# 7Seg.net
KiCad netlist of a schematic drawn in Altium Designer
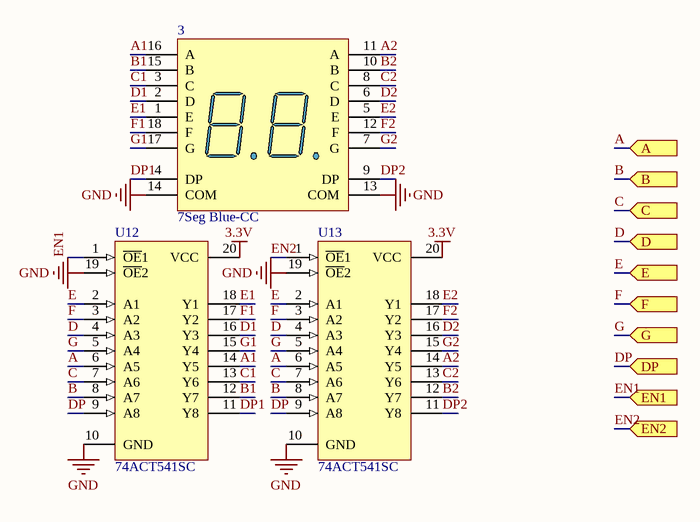
[diagram p0: 7Seg.SchDoc]

(export (version "E")
  (design (tool "Eeschema 10.0.6"))
  (components
    (comp (ref "3")
      (value "7Seg Blue-CC")
      (footprint "7Segment Dual")
      (description "General Purpose Blue 7-Segment Display: CC, RH DP, Gray Surface")
      (fields (field (name "PUBLISHER") "Altium Limited"))
      (libsource (lib "KN2CLib") (part "7Seg Blue-CC_Dual"))
    )
    (comp (ref "U12")
      (value "74ACT541SC")
      (footprint "M20B_N")
      (description "Octal Buffer/Line Driver with 3-State Output")
      (fields (field (name "PUBLISHER") "Altium Limited"))
      (libsource (lib "FSC Logic Buffer Line Driver") (part "74ACT541SC"))
    )
    (comp (ref "U13")
      (value "74ACT541SC")
      (footprint "M20B_N")
      (description "Octal Buffer/Line Driver with 3-State Output")
      (fields (field (name "PUBLISHER") "Altium Limited"))
      (libsource (lib "FSC Logic Buffer Line Driver") (part "74ACT541SC"))
    )
  )
  (nets
    (net (code "1") (name "/A") (class "Default")
      (node (ref "U12") (pin "6") (pinfunction "A5_6") (pintype "input"))
      (node (ref "U13") (pin "6") (pinfunction "A5_6") (pintype "input"))
    )
    (net (code "2") (name "/A1") (class "Default")
      (node (ref "3") (pin "16") (pinfunction "A_16") (pintype "passive"))
      (node (ref "U12") (pin "14") (pinfunction "Y5_14") (pintype "tri_state"))
    )
    (net (code "3") (name "/A2") (class "Default")
      (node (ref "3") (pin "11") (pinfunction "A_11") (pintype "passive"))
      (node (ref "U13") (pin "14") (pinfunction "Y5_14") (pintype "tri_state"))
    )
    (net (code "4") (name "/B") (class "Default")
      (node (ref "U12") (pin "8") (pinfunction "A7_8") (pintype "input"))
      (node (ref "U13") (pin "8") (pinfunction "A7_8") (pintype "input"))
    )
    (net (code "5") (name "/B1") (class "Default")
      (node (ref "3") (pin "15") (pinfunction "B_15") (pintype "passive"))
      (node (ref "U12") (pin "12") (pinfunction "Y7_12") (pintype "tri_state"))
    )
    (net (code "6") (name "/B2") (class "Default")
      (node (ref "3") (pin "10") (pinfunction "B_10") (pintype "passive"))
      (node (ref "U13") (pin "12") (pinfunction "Y7_12") (pintype "tri_state"))
    )
    (net (code "7") (name "/C") (class "Default")
      (node (ref "U12") (pin "7") (pinfunction "A6_7") (pintype "input"))
      (node (ref "U13") (pin "7") (pinfunction "A6_7") (pintype "input"))
    )
    (net (code "8") (name "/C1") (class "Default")
      (node (ref "3") (pin "3") (pinfunction "C_3") (pintype "passive"))
      (node (ref "U12") (pin "13") (pinfunction "Y6_13") (pintype "tri_state"))
    )
    (net (code "9") (name "/C2") (class "Default")
      (node (ref "3") (pin "8") (pinfunction "C_8") (pintype "passive"))
      (node (ref "U13") (pin "13") (pinfunction "Y6_13") (pintype "tri_state"))
    )
    (net (code "10") (name "/D") (class "Default")
      (node (ref "U12") (pin "4") (pinfunction "A3_4") (pintype "input"))
      (node (ref "U13") (pin "4") (pinfunction "A3_4") (pintype "input"))
    )
    (net (code "11") (name "/D1") (class "Default")
      (node (ref "3") (pin "2") (pinfunction "D_2") (pintype "passive"))
      (node (ref "U12") (pin "16") (pinfunction "Y3_16") (pintype "tri_state"))
    )
    (net (code "12") (name "/D2") (class "Default")
      (node (ref "3") (pin "6") (pinfunction "D_6") (pintype "passive"))
      (node (ref "U13") (pin "16") (pinfunction "Y3_16") (pintype "tri_state"))
    )
    (net (code "13") (name "/DP") (class "Default")
      (node (ref "U12") (pin "9") (pinfunction "A8_9") (pintype "input"))
      (node (ref "U13") (pin "9") (pinfunction "A8_9") (pintype "input"))
    )
    (net (code "14") (name "/DP1") (class "Default")
      (node (ref "3") (pin "4") (pinfunction "DP_4") (pintype "passive"))
      (node (ref "U12") (pin "11") (pinfunction "Y8_11") (pintype "tri_state"))
    )
    (net (code "15") (name "/DP2") (class "Default")
      (node (ref "3") (pin "9") (pinfunction "DP_9") (pintype "passive"))
      (node (ref "U13") (pin "11") (pinfunction "Y8_11") (pintype "tri_state"))
    )
    (net (code "16") (name "/E") (class "Default")
      (node (ref "U12") (pin "2") (pinfunction "A1_2") (pintype "input"))
      (node (ref "U13") (pin "2") (pinfunction "A1_2") (pintype "input"))
    )
    (net (code "17") (name "/E1") (class "Default")
      (node (ref "3") (pin "1") (pinfunction "E_1") (pintype "passive"))
      (node (ref "U12") (pin "18") (pinfunction "Y1_18") (pintype "tri_state"))
    )
    (net (code "18") (name "/E2") (class "Default")
      (node (ref "3") (pin "5") (pinfunction "E_5") (pintype "passive"))
      (node (ref "U13") (pin "18") (pinfunction "Y1_18") (pintype "tri_state"))
    )
    (net (code "19") (name "/EN1") (class "Default")
      (node (ref "U12") (pin "1") (pinfunction "~{OE}1_1") (pintype "input"))
    )
    (net (code "20") (name "/EN2") (class "Default")
      (node (ref "U13") (pin "1") (pinfunction "~{OE}1_1") (pintype "input"))
    )
    (net (code "21") (name "/F") (class "Default")
      (node (ref "U12") (pin "3") (pinfunction "A2_3") (pintype "input"))
      (node (ref "U13") (pin "3") (pinfunction "A2_3") (pintype "input"))
    )
    (net (code "22") (name "/F1") (class "Default")
      (node (ref "3") (pin "18") (pinfunction "F_18") (pintype "passive"))
      (node (ref "U12") (pin "17") (pinfunction "Y2_17") (pintype "tri_state"))
    )
    (net (code "23") (name "/F2") (class "Default")
      (node (ref "3") (pin "12") (pinfunction "F_12") (pintype "passive"))
      (node (ref "U13") (pin "17") (pinfunction "Y2_17") (pintype "tri_state"))
    )
    (net (code "24") (name "/G") (class "Default")
      (node (ref "U12") (pin "5") (pinfunction "A4_5") (pintype "input"))
      (node (ref "U13") (pin "5") (pinfunction "A4_5") (pintype "input"))
    )
    (net (code "25") (name "/G1") (class "Default")
      (node (ref "3") (pin "17") (pinfunction "G_17") (pintype "passive"))
      (node (ref "U12") (pin "15") (pinfunction "Y4_15") (pintype "tri_state"))
    )
    (net (code "26") (name "/G2") (class "Default")
      (node (ref "3") (pin "7") (pinfunction "G_7") (pintype "passive"))
      (node (ref "U13") (pin "15") (pinfunction "Y4_15") (pintype "tri_state"))
    )
    (net (code "27") (name "3.3V") (class "Default")
      (node (ref "U12") (pin "20") (pinfunction "VCC_20") (pintype "power_in"))
      (node (ref "U13") (pin "20") (pinfunction "VCC_20") (pintype "power_in"))
    )
    (net (code "28") (name "GND") (class "Default")
      (node (ref "3") (pin "13") (pinfunction "COM_13") (pintype "passive"))
      (node (ref "3") (pin "14") (pinfunction "COM_14") (pintype "passive"))
      (node (ref "U12") (pin "10") (pinfunction "GND_10") (pintype "power_in"))
      (node (ref "U12") (pin "19") (pinfunction "~{OE}2_19") (pintype "input"))
      (node (ref "U13") (pin "10") (pinfunction "GND_10") (pintype "power_in"))
      (node (ref "U13") (pin "19") (pinfunction "~{OE}2_19") (pintype "input"))
    )
  )
)
